# LCmeter0-LCD-8pinlcd-alt2.net
KiCad netlist of a schematic drawn in EAGLE
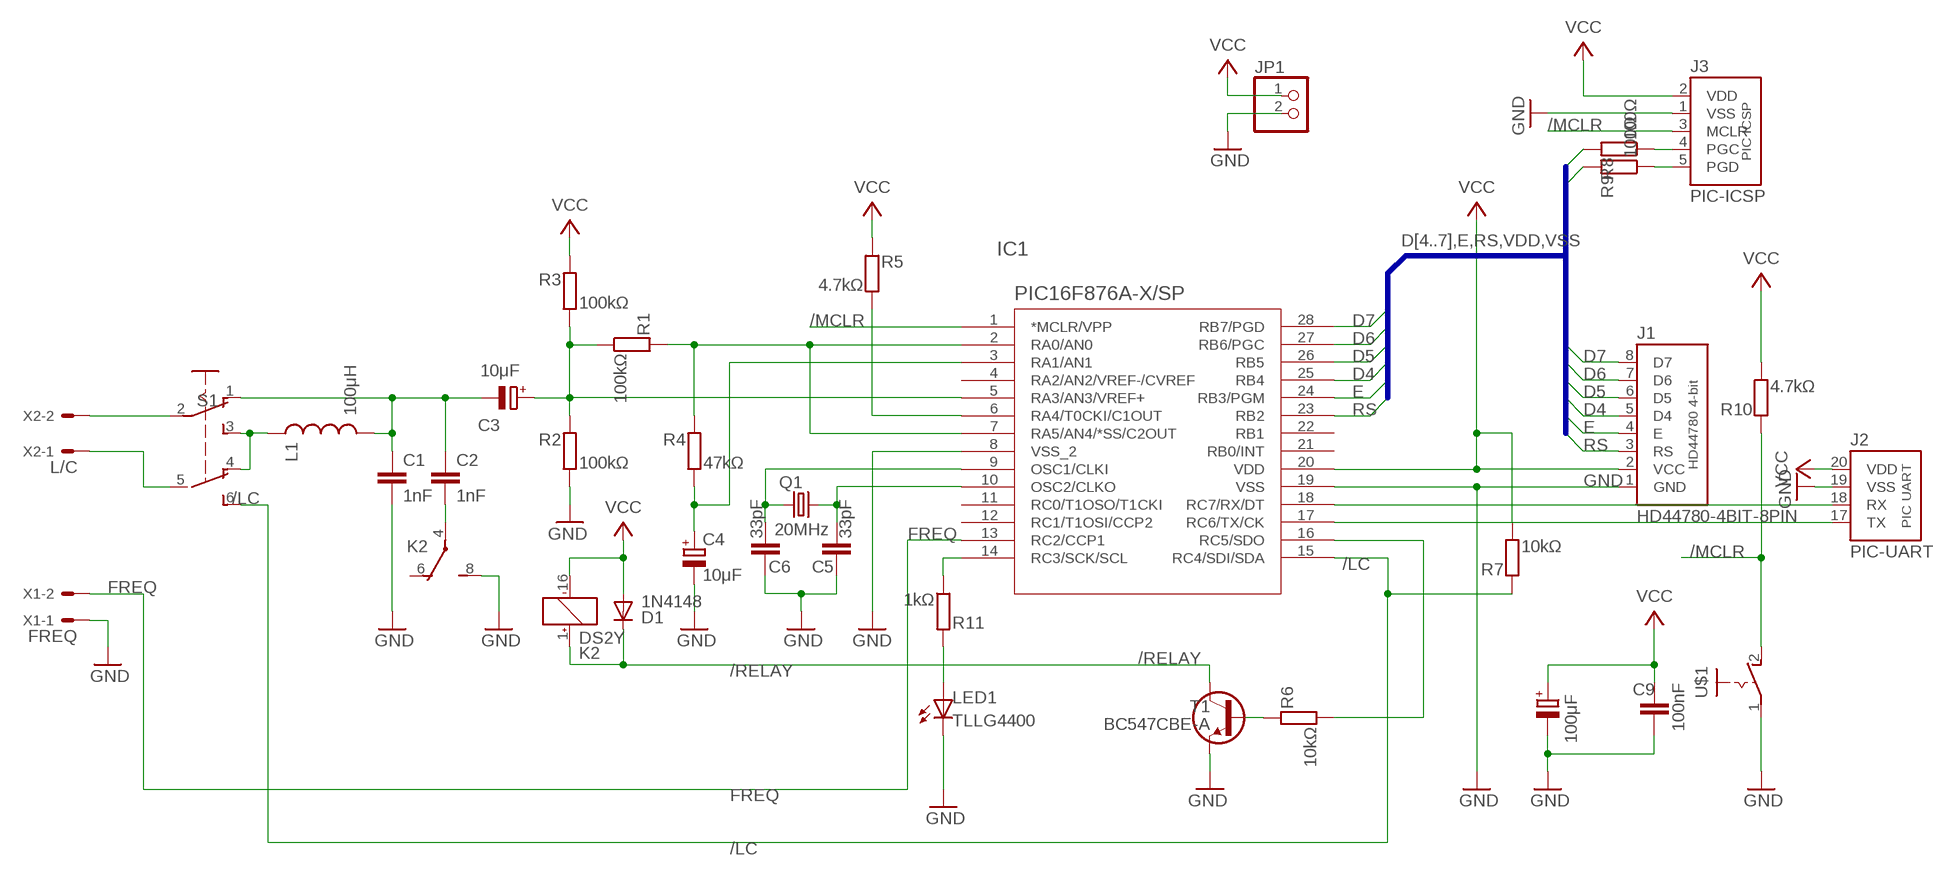
[diagram p0: schematic, sheet 1]

(export (version "E")
  (design (tool "Eeschema 10.0.6"))
  (components
    (comp (ref "C1")
      (value "1nF")
      (footprint "eagle-import:C050-020X036")
      (libsource (lib "eagle-import") (part "C050-020X036"))
    )
    (comp (ref "C2")
      (value "1nF")
      (footprint "eagle-import:C050-020X036")
      (libsource (lib "eagle-import") (part "C050-020X036"))
    )
    (comp (ref "C3")
      (value "10μF")
      (footprint "eagle-import:E2,5-4")
      (libsource (lib "eagle-import") (part "CPOLE2,5-4"))
    )
    (comp (ref "C4")
      (value "10μF")
      (footprint "eagle-import:E2,5-4")
      (libsource (lib "eagle-import") (part "CPOLE2,5-4"))
    )
    (comp (ref "C5")
      (value "33pF")
      (footprint "eagle-import:C025-020X036")
      (libsource (lib "eagle-import") (part "C025-020X036"))
    )
    (comp (ref "C6")
      (value "33pF")
      (footprint "eagle-import:C025-020X036")
      (libsource (lib "eagle-import") (part "C025-020X036"))
    )
    (comp (ref "C7")
      (value "100μF")
      (footprint "eagle-import:E2,5-6")
      (libsource (lib "eagle-import") (part "CPOLE2.5-6"))
    )
    (comp (ref "C9")
      (value "100nF")
      (footprint "eagle-import:C025-024X044")
      (libsource (lib "eagle-import") (part "C-EU025-024X044"))
    )
    (comp (ref "D1")
      (value "1N4148")
      (footprint "eagle-import:DO34-7")
      (libsource (lib "eagle-import") (part "1N414834-7"))
    )
    (comp (ref "IC1")
      (value "PIC16F876A-X/SP")
      (footprint "eagle-import:DIL28-3")
      (libsource (lib "eagle-import") (part "PIC16F876A-X/SP"))
    )
    (comp (ref "J1")
      (value "HD44780-4BIT-8PIN")
      (footprint "eagle-import:CONN-8P")
      (libsource (lib "eagle-import") (part "HD44780-4BIT-8PIN"))
    )
    (comp (ref "J2")
      (value "PIC-UART")
      (footprint "eagle-import:PIC-UART")
      (libsource (lib "eagle-import") (part "PIC-UART"))
    )
    (comp (ref "J3")
      (value "PIC-ICSP")
      (footprint "eagle-import:CONN-5P")
      (libsource (lib "eagle-import") (part "PIC-ICSP"))
    )
    (comp (ref "JP1")
      (value "PINHD-1X2")
      (footprint "eagle-import:1X02")
      (libsource (lib "eagle-import") (part "PINHD-1X2"))
    )
    (comp (ref "K2")
      (value "DS2Y")
      (footprint "eagle-import:DS2Y")
      (fields (field (name "MPN") "DS2Y-S-DC5V"))
      (libsource (lib "eagle-import") (part "DS2Y-S-DC5V"))
    )
    (comp (ref "L1")
      (value "100μH")
      (footprint "eagle-import:L-8R")
      (libsource (lib "eagle-import") (part "L-09R"))
    )
    (comp (ref "LED1")
      (value "TLLG4400")
      (footprint "eagle-import:LED3MM")
      (fields (field (name "MF") "VISHAY SEMICONDUCTOR"))
      (libsource (lib "eagle-import") (part "TLLG4400"))
    )
    (comp (ref "Q1")
      (value "20MHz")
      (footprint "eagle-import:HC49")
      (libsource (lib "eagle-import") (part "CRYSTALHC49"))
    )
    (comp (ref "R1")
      (value "100kΩ")
      (footprint "eagle-import:0202_7")
      (libsource (lib "eagle-import") (part "R0202/7"))
    )
    (comp (ref "R2")
      (value "100kΩ")
      (footprint "eagle-import:0202_7")
      (libsource (lib "eagle-import") (part "R0202/7"))
    )
    (comp (ref "R3")
      (value "100kΩ")
      (footprint "eagle-import:0202_7")
      (libsource (lib "eagle-import") (part "R0202/7"))
    )
    (comp (ref "R4")
      (value "47kΩ")
      (footprint "eagle-import:0202_7")
      (libsource (lib "eagle-import") (part "R0202/7"))
    )
    (comp (ref "R5")
      (value "4.7kΩ")
      (footprint "eagle-import:0202_7")
      (libsource (lib "eagle-import") (part "R0202/7"))
    )
    (comp (ref "R6")
      (value "10kΩ")
      (footprint "eagle-import:0202_7")
      (libsource (lib "eagle-import") (part "R0202/7"))
    )
    (comp (ref "R7")
      (value "10kΩ")
      (footprint "eagle-import:0202_10")
      (libsource (lib "eagle-import") (part "R0202/10"))
    )
    (comp (ref "R8")
      (value "100Ω")
      (footprint "eagle-import:0202_5")
      (libsource (lib "eagle-import") (part "R0202/5"))
    )
    (comp (ref "R9")
      (value "100Ω")
      (footprint "eagle-import:0202_5")
      (libsource (lib "eagle-import") (part "R0202/5"))
    )
    (comp (ref "R10")
      (value "4.7kΩ")
      (footprint "eagle-import:0202_7")
      (libsource (lib "eagle-import") (part "R0202/7"))
    )
    (comp (ref "R11")
      (value "1kΩ")
      (footprint "eagle-import:0202_5")
      (libsource (lib "eagle-import") (part "R0202/5"))
    )
    (comp (ref "S1")
      (value "SL-SW-2P-2T")
      (footprint "eagle-import:SLSW-2P2T")
      (libsource (lib "eagle-import") (part "SL-SW-2P-2T"))
    )
    (comp (ref "T1")
      (value "BC547CBE-A")
      (footprint "eagle-import:TO92-CBE-A")
      (libsource (lib "eagle-import") (part "BC547CBE-A"))
    )
    (comp (ref "U$1")
      (value "PB-1P-1T")
      (footprint "eagle-import:PB-1P1T")
      (libsource (lib "eagle-import") (part "PB-1P-1T"))
    )
    (comp (ref "X1")
      (value "FREQ")
      (footprint "eagle-import:70543-02")
      (libsource (lib "eagle-import") (part "C-GRID-02-70543"))
    )
    (comp (ref "X2")
      (value "L/C")
      (footprint "eagle-import:70543-02")
      (libsource (lib "eagle-import") (part "C-GRID-02-70543"))
    )
  )
  (nets
    (net (code "3") (name "/D4") (class "Default")
      (node (ref "IC1") (pin "25") (pinfunction "RB4_25") (pintype "passive"))
      (node (ref "J1") (pin "5") (pinfunction "D4_5") (pintype "passive"))
    )
    (net (code "4") (name "/D5") (class "Default")
      (node (ref "IC1") (pin "26") (pinfunction "RB5_26") (pintype "passive"))
      (node (ref "J1") (pin "6") (pinfunction "D5_6") (pintype "passive"))
    )
    (net (code "5") (name "/D6") (class "Default")
      (node (ref "IC1") (pin "27") (pinfunction "RB6/PGC_27") (pintype "passive"))
      (node (ref "J1") (pin "7") (pinfunction "D6_7") (pintype "passive"))
      (node (ref "R9") (pin "2") (pinfunction "2_2") (pintype "passive"))
    )
    (net (code "6") (name "/D7") (class "Default")
      (node (ref "IC1") (pin "28") (pinfunction "RB7/PGD_28") (pintype "passive"))
      (node (ref "J1") (pin "8") (pinfunction "D7_8") (pintype "passive"))
      (node (ref "R8") (pin "2") (pinfunction "2_2") (pintype "passive"))
    )
    (net (code "7") (name "/E") (class "Default")
      (node (ref "IC1") (pin "24") (pinfunction "RB3/PGM_24") (pintype "passive"))
      (node (ref "J1") (pin "4") (pinfunction "E_4") (pintype "passive"))
    )
    (net (code "8") (name "/FREQ") (class "Default")
      (node (ref "IC1") (pin "13") (pinfunction "RC2/CCP1_13") (pintype "passive"))
      (node (ref "X1") (pin "2") (pinfunction "S_2") (pintype "passive"))
    )
    (net (code "9") (name "/RS") (class "Default")
      (node (ref "IC1") (pin "23") (pinfunction "RB2_23") (pintype "passive"))
      (node (ref "J1") (pin "3") (pinfunction "RS_3") (pintype "passive"))
    )
    (net (code "11") (name "/{slash}LC") (class "Default")
      (node (ref "IC1") (pin "15") (pinfunction "RC4/SDI/SDA_15") (pintype "passive"))
      (node (ref "R7") (pin "2") (pinfunction "2_2") (pintype "passive"))
      (node (ref "S1") (pin "6") (pinfunction "S1_6") (pintype "passive"))
    )
    (net (code "12") (name "/{slash}MCLR") (class "Default")
      (node (ref "IC1") (pin "1") (pinfunction "*MCLR/VPP_1") (pintype "passive"))
      (node (ref "J3") (pin "3") (pinfunction "MCLR_3") (pintype "passive"))
      (node (ref "R10") (pin "2") (pinfunction "2_2") (pintype "passive"))
      (node (ref "U$1") (pin "2") (pinfunction "S_2") (pintype "passive"))
    )
    (net (code "13") (name "/{slash}RELAY") (class "Default")
      (node (ref "D1") (pin "C") (pinfunction "C_C") (pintype "passive"))
      (node (ref "K2") (pin "1") (pinfunction "+_1") (pintype "passive"))
      (node (ref "T1") (pin "C") (pinfunction "C_C") (pintype "passive"))
    )
    (net (code "14") (name "GND") (class "Default")
      (node (ref "C1") (pin "2") (pinfunction "2_2") (pintype "passive"))
      (node (ref "C4") (pin "-") (pinfunction "-_-") (pintype "passive"))
      (node (ref "C5") (pin "1") (pinfunction "1_1") (pintype "passive"))
      (node (ref "C6") (pin "1") (pinfunction "1_1") (pintype "passive"))
      (node (ref "C7") (pin "-") (pinfunction "-_-") (pintype "passive"))
      (node (ref "C9") (pin "2") (pinfunction "2_2") (pintype "passive"))
      (node (ref "IC1") (pin "19") (pinfunction "VSS_19") (pintype "passive"))
      (node (ref "IC1") (pin "8") (pinfunction "VSS_2_8") (pintype "passive"))
      (node (ref "J1") (pin "1") (pinfunction "GND_1") (pintype "passive"))
      (node (ref "J2") (pin "19") (pinfunction "VSS_19") (pintype "passive"))
      (node (ref "J3") (pin "1") (pinfunction "VSS_1") (pintype "passive"))
      (node (ref "JP1") (pin "2") (pinfunction "2_2") (pintype "passive"))
      (node (ref "K2") (pin "8") (pinfunction "S_8") (pintype "passive"))
      (node (ref "LED1") (pin "K") (pinfunction "C_K") (pintype "passive"))
      (node (ref "R2") (pin "1") (pinfunction "1_1") (pintype "passive"))
      (node (ref "T1") (pin "E") (pinfunction "E_E") (pintype "passive"))
      (node (ref "U$1") (pin "1") (pinfunction "P_1") (pintype "passive"))
      (node (ref "X1") (pin "1") (pinfunction "S_1") (pintype "passive"))
    )
    (net (code "15") (name "Net-(IC1-OSC1{slash}CLKI)") (class "Default")
      (node (ref "C6") (pin "2") (pinfunction "2_2") (pintype "passive"))
      (node (ref "IC1") (pin "9") (pinfunction "OSC1/CLKI_9") (pintype "passive"))
      (node (ref "Q1") (pin "1") (pinfunction "1_1") (pintype "passive"))
    )
    (net (code "16") (name "Net-(IC1-OSC2{slash}CLKO)") (class "Default")
      (node (ref "C5") (pin "2") (pinfunction "2_2") (pintype "passive"))
      (node (ref "IC1") (pin "10") (pinfunction "OSC2/CLKO_10") (pintype "passive"))
      (node (ref "Q1") (pin "2") (pinfunction "2_2") (pintype "passive"))
    )
    (net (code "17") (name "Net-(IC1-RA0{slash}AN0)") (class "Default")
      (node (ref "IC1") (pin "2") (pinfunction "RA0/AN0_2") (pintype "passive"))
      (node (ref "IC1") (pin "7") (pinfunction "RA5/AN4/*SS/C2OUT_7") (pintype "passive"))
      (node (ref "R1") (pin "2") (pinfunction "2_2") (pintype "passive"))
      (node (ref "R4") (pin "2") (pinfunction "2_2") (pintype "passive"))
    )
    (net (code "18") (name "Net-(IC1-RA1{slash}AN1)") (class "Default")
      (node (ref "C4") (pin "+") (pinfunction "+_+") (pintype "passive"))
      (node (ref "IC1") (pin "3") (pinfunction "RA1/AN1_3") (pintype "passive"))
      (node (ref "R4") (pin "1") (pinfunction "1_1") (pintype "passive"))
    )
    (net (code "19") (name "Net-(IC1-RA3{slash}AN3{slash}VREF+)") (class "Default")
      (node (ref "C3") (pin "+") (pinfunction "+_+") (pintype "passive"))
      (node (ref "IC1") (pin "5") (pinfunction "RA3/AN3/VREF+_5") (pintype "passive"))
      (node (ref "R1") (pin "1") (pinfunction "1_1") (pintype "passive"))
      (node (ref "R2") (pin "2") (pinfunction "2_2") (pintype "passive"))
      (node (ref "R3") (pin "1") (pinfunction "1_1") (pintype "passive"))
    )
    (net (code "20") (name "Net-(IC1-RA4{slash}T0CKI{slash}C1OUT)") (class "Default")
      (node (ref "IC1") (pin "6") (pinfunction "RA4/T0CKI/C1OUT_6") (pintype "passive"))
      (node (ref "R5") (pin "1") (pinfunction "1_1") (pintype "passive"))
    )
    (net (code "21") (name "Net-(IC1-RC3{slash}SCK{slash}SCL)") (class "Default")
      (node (ref "IC1") (pin "14") (pinfunction "RC3/SCK/SCL_14") (pintype "passive"))
      (node (ref "R11") (pin "1") (pinfunction "1_1") (pintype "passive"))
    )
    (net (code "22") (name "Net-(IC1-RC5{slash}SDO)") (class "Default")
      (node (ref "IC1") (pin "16") (pinfunction "RC5/SDO_16") (pintype "passive"))
      (node (ref "R6") (pin "1") (pinfunction "1_1") (pintype "passive"))
    )
    (net (code "23") (name "Net-(IC1-RC6{slash}TX{slash}CK)") (class "Default")
      (node (ref "IC1") (pin "17") (pinfunction "RC6/TX/CK_17") (pintype "passive"))
      (node (ref "J2") (pin "17") (pinfunction "TX_17") (pintype "passive"))
    )
    (net (code "24") (name "Net-(IC1-RC7{slash}RX{slash}DT)") (class "Default")
      (node (ref "IC1") (pin "18") (pinfunction "RC7/RX/DT_18") (pintype "passive"))
      (node (ref "J2") (pin "18") (pinfunction "RX_18") (pintype "passive"))
    )
    (net (code "25") (name "Net-(J3-PGC)") (class "Default")
      (node (ref "J3") (pin "4") (pinfunction "PGC_4") (pintype "passive"))
      (node (ref "R8") (pin "1") (pinfunction "1_1") (pintype "passive"))
    )
    (net (code "26") (name "Net-(J3-PGD)") (class "Default")
      (node (ref "J3") (pin "5") (pinfunction "PGD_5") (pintype "passive"))
      (node (ref "R9") (pin "1") (pinfunction "1_1") (pintype "passive"))
    )
    (net (code "27") (name "Net-(K2B-P)") (class "Default")
      (node (ref "C2") (pin "2") (pinfunction "2_2") (pintype "passive"))
      (node (ref "K2") (pin "4") (pinfunction "P_4") (pintype "passive"))
    )
    (net (code "28") (name "Net-(L1-1)") (class "Default")
      (node (ref "L1") (pin "P$1") (pinfunction "1_P$1") (pintype "passive"))
      (node (ref "S1") (pin "3") (pinfunction "S_3") (pintype "passive"))
      (node (ref "S1") (pin "4") (pinfunction "O1_4") (pintype "passive"))
    )
    (net (code "29") (name "Net-(L1-2)") (class "Default")
      (node (ref "C1") (pin "1") (pinfunction "1_1") (pintype "passive"))
      (node (ref "C2") (pin "1") (pinfunction "1_1") (pintype "passive"))
      (node (ref "C3") (pin "-") (pinfunction "-_-") (pintype "passive"))
      (node (ref "L1") (pin "P$2") (pinfunction "2_P$2") (pintype "passive"))
      (node (ref "S1") (pin "1") (pinfunction "O_1") (pintype "passive"))
    )
    (net (code "30") (name "Net-(LED1-PadA)") (class "Default")
      (node (ref "LED1") (pin "A") (pinfunction "A_A") (pintype "passive"))
      (node (ref "R11") (pin "2") (pinfunction "2_2") (pintype "passive"))
    )
    (net (code "31") (name "Net-(R6-Pad2)") (class "Default")
      (node (ref "R6") (pin "2") (pinfunction "2_2") (pintype "passive"))
      (node (ref "T1") (pin "B") (pinfunction "B_B") (pintype "passive"))
    )
    (net (code "32") (name "Net-(S1-P)") (class "Default")
      (node (ref "S1") (pin "2") (pinfunction "P_2") (pintype "passive"))
      (node (ref "X2") (pin "2") (pinfunction "S_2") (pintype "passive"))
    )
    (net (code "33") (name "Net-(S1-P1)") (class "Default")
      (node (ref "S1") (pin "5") (pinfunction "P1_5") (pintype "passive"))
      (node (ref "X2") (pin "1") (pinfunction "S_1") (pintype "passive"))
    )
    (net (code "34") (name "VCC") (class "Default")
      (node (ref "C7") (pin "+") (pinfunction "+_+") (pintype "passive"))
      (node (ref "C9") (pin "1") (pinfunction "1_1") (pintype "passive"))
      (node (ref "D1") (pin "A") (pinfunction "A_A") (pintype "passive"))
      (node (ref "IC1") (pin "20") (pinfunction "VDD_20") (pintype "passive"))
      (node (ref "J1") (pin "2") (pinfunction "VCC_2") (pintype "passive"))
      (node (ref "J2") (pin "20") (pinfunction "VDD_20") (pintype "passive"))
      (node (ref "J3") (pin "2") (pinfunction "VDD_2") (pintype "passive"))
      (node (ref "JP1") (pin "1") (pinfunction "1_1") (pintype "passive"))
      (node (ref "K2") (pin "16") (pinfunction "-_16") (pintype "passive"))
      (node (ref "R10") (pin "1") (pinfunction "1_1") (pintype "passive"))
      (node (ref "R3") (pin "2") (pinfunction "2_2") (pintype "passive"))
      (node (ref "R5") (pin "2") (pinfunction "2_2") (pintype "passive"))
      (node (ref "R7") (pin "1") (pinfunction "1_1") (pintype "passive"))
    )
    (net (code "35") (name "unconnected-(IC1-RA2{slash}AN2{slash}VREF-{slash}CVREF-Pad4)") (class "Default")
      (node (ref "IC1") (pin "4") (pinfunction "RA2/AN2/VREF-/CVREF_4") (pintype "passive"))
    )
    (net (code "36") (name "unconnected-(IC1-RB0{slash}INT-Pad21)") (class "Default")
      (node (ref "IC1") (pin "21") (pinfunction "RB0/INT_21") (pintype "passive"))
    )
    (net (code "37") (name "unconnected-(IC1-RB1-Pad22)") (class "Default")
      (node (ref "IC1") (pin "22") (pinfunction "RB1_22") (pintype "passive"))
    )
    (net (code "38") (name "unconnected-(IC1-RC0{slash}T1OSO{slash}T1CKI-Pad11)") (class "Default")
      (node (ref "IC1") (pin "11") (pinfunction "RC0/T1OSO/T1CKI_11") (pintype "passive"))
    )
    (net (code "39") (name "unconnected-(IC1-RC1{slash}T1OSI{slash}CCP2-Pad12)") (class "Default")
      (node (ref "IC1") (pin "12") (pinfunction "RC1/T1OSI/CCP2_12") (pintype "passive"))
    )
    (net (code "40") (name "unconnected-(K2B-O-Pad6)") (class "Default")
      (node (ref "K2") (pin "6") (pinfunction "O_6") (pintype "passive"))
    )
  )
)
